# TTL.net
KiCad netlist of a schematic drawn in Altium Designer
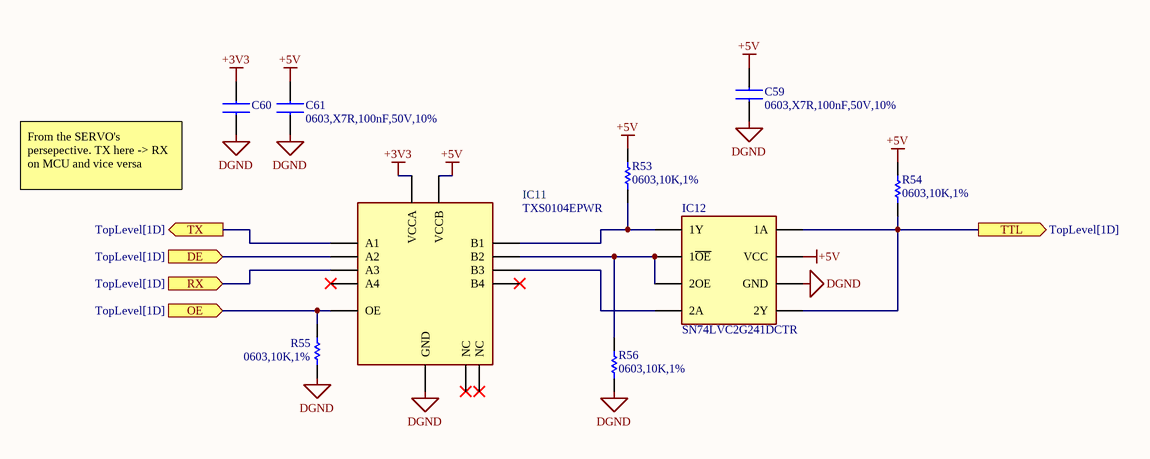
[diagram p0: TTL.SchDoc]

(export (version "E")
  (design (tool "Eeschema 10.0.6"))
  (components
    (comp (ref "C59")
      (value "0603,X7R,100nF,50V,10%")
      (footprint "CAPC1608X90N")
      (description "50V 100nF X7R ±10% 0603 Multilayer Ceramic Capacitors MLCC - SMD/SMT ROHS")
      (fields (field (name "LCSC PART #") "C14663") (field (name "MANU PART #") "CC0603KRX7R9BB104"))
      (libsource (lib "flight-controller") (part "CC0603KRX7R9BB104"))
    )
    (comp (ref "C60")
      (value "0603,X7R,100nF,50V,10%")
      (footprint "CAPC1608X90N")
      (description "50V 100nF X7R ±10% 0603 Multilayer Ceramic Capacitors MLCC - SMD/SMT ROHS")
      (fields (field (name "LCSC PART #") "C14663") (field (name "MANU PART #") "CC0603KRX7R9BB104"))
      (libsource (lib "flight-controller") (part "CC0603KRX7R9BB104"))
    )
    (comp (ref "C61")
      (value "0603,X7R,100nF,50V,10%")
      (footprint "CAPC1608X90N")
      (description "50V 100nF X7R ±10% 0603 Multilayer Ceramic Capacitors MLCC - SMD/SMT ROHS")
      (fields (field (name "LCSC PART #") "C14663") (field (name "MANU PART #") "CC0603KRX7R9BB104"))
      (libsource (lib "flight-controller") (part "CC0603KRX7R9BB104"))
    )
    (comp (ref "IC11")
      (value "TXS0104EPWR")
      (footprint "TXB0104PWR")
      (description "4-Bit Bidirectional Voltage-Level Translator For Open-Drain and Push-Pull Applications")
      (fields (field (name "LCSC PART #") "C44955"))
      (libsource (lib "flight-controller") (part "TXS0104EPWR"))
    )
    (comp (ref "IC12")
      (value "SN74LVC2G241DCTR")
      (footprint "SOP65P400X130-8N")
      (description "SN74LVC2G241 Dual Buffer and Driver with Three-State Outputs")
      (fields (field (name "LCSC PART #") "C2676069"))
      (libsource (lib "flight-controller") (part "SN74LVC2G241DCTR"))
    )
    (comp (ref "R53")
      (value "0603,10K,1%")
      (footprint "RESC1608X90N")
      (description "100mW Thick Film Resistor 75V ±100ppm/℃ ±1% 10kΩ 0603 Chip Resistor - Surface Mount ROHS")
      (fields (field (name "LCSC PART #") "C25804") (field (name "MANU PART #") "0603WAF1002T5E"))
      (libsource (lib "flight-controller") (part "0603WAF1002T5E"))
    )
    (comp (ref "R54")
      (value "0603,10K,1%")
      (footprint "RESC1608X90N")
      (description "100mW Thick Film Resistor 75V ±100ppm/℃ ±1% 10kΩ 0603 Chip Resistor - Surface Mount ROHS")
      (fields (field (name "LCSC PART #") "C25804") (field (name "MANU PART #") "0603WAF1002T5E"))
      (libsource (lib "flight-controller") (part "0603WAF1002T5E"))
    )
    (comp (ref "R55")
      (value "0603,10K,1%")
      (footprint "RESC1608X90N")
      (description "100mW Thick Film Resistor 75V ±100ppm/℃ ±1% 10kΩ 0603 Chip Resistor - Surface Mount ROHS")
      (fields (field (name "LCSC PART #") "C25804") (field (name "MANU PART #") "0603WAF1002T5E"))
      (libsource (lib "flight-controller") (part "0603WAF1002T5E"))
    )
    (comp (ref "R56")
      (value "0603,10K,1%")
      (footprint "RESC1608X90N")
      (description "100mW Thick Film Resistor 75V ±100ppm/℃ ±1% 10kΩ 0603 Chip Resistor - Surface Mount ROHS")
      (fields (field (name "LCSC PART #") "C25804") (field (name "MANU PART #") "0603WAF1002T5E"))
      (libsource (lib "flight-controller") (part "0603WAF1002T5E"))
    )
  )
  (nets
    (net (code "1") (name "+3V3") (class "Default")
      (node (ref "C60") (pin "2") (pinfunction "2_2") (pintype "passive"))
      (node (ref "IC11") (pin "1") (pinfunction "VCCA_1") (pintype "passive"))
    )
    (net (code "2") (name "+5V") (class "Default")
      (node (ref "C59") (pin "2") (pinfunction "2_2") (pintype "passive"))
      (node (ref "C61") (pin "2") (pinfunction "2_2") (pintype "passive"))
      (node (ref "IC11") (pin "14") (pinfunction "VCCB_14") (pintype "passive"))
      (node (ref "IC12") (pin "8") (pinfunction "VCC_8") (pintype "passive"))
      (node (ref "R53") (pin "2") (pinfunction "2_2") (pintype "passive"))
      (node (ref "R54") (pin "2") (pinfunction "2_2") (pintype "passive"))
    )
    (net (code "3") (name "/DE") (class "Default")
      (node (ref "IC11") (pin "3") (pinfunction "A2_3") (pintype "passive"))
    )
    (net (code "4") (name "/OE") (class "Default")
      (node (ref "IC11") (pin "8") (pinfunction "OE_8") (pintype "passive"))
      (node (ref "R55") (pin "2") (pinfunction "2_2") (pintype "passive"))
    )
    (net (code "5") (name "/RX") (class "Default")
      (node (ref "IC11") (pin "4") (pinfunction "A3_4") (pintype "passive"))
    )
    (net (code "6") (name "/TTL") (class "Default")
      (node (ref "IC12") (pin "2") (pinfunction "1A_2") (pintype "passive"))
      (node (ref "IC12") (pin "3") (pinfunction "2Y_3") (pintype "passive"))
      (node (ref "R54") (pin "1") (pinfunction "1_1") (pintype "passive"))
    )
    (net (code "7") (name "/TX") (class "Default")
      (node (ref "IC11") (pin "2") (pinfunction "A1_2") (pintype "passive"))
    )
    (net (code "8") (name "DGND") (class "Default")
      (node (ref "C59") (pin "1") (pinfunction "1_1") (pintype "passive"))
      (node (ref "C60") (pin "1") (pinfunction "1_1") (pintype "passive"))
      (node (ref "C61") (pin "1") (pinfunction "1_1") (pintype "passive"))
      (node (ref "IC11") (pin "7") (pinfunction "GND_7") (pintype "passive"))
      (node (ref "IC12") (pin "4") (pinfunction "GND_4") (pintype "passive"))
      (node (ref "R55") (pin "1") (pinfunction "1_1") (pintype "passive"))
      (node (ref "R56") (pin "1") (pinfunction "1_1") (pintype "passive"))
    )
    (net (code "9") (name "Net-(IC11-B1)") (class "Default")
      (node (ref "IC11") (pin "13") (pinfunction "B1_13") (pintype "passive"))
      (node (ref "IC12") (pin "6") (pinfunction "1Y_6") (pintype "passive"))
      (node (ref "R53") (pin "1") (pinfunction "1_1") (pintype "passive"))
    )
    (net (code "10") (name "Net-(IC11-B2)") (class "Default")
      (node (ref "IC11") (pin "12") (pinfunction "B2_12") (pintype "passive"))
      (node (ref "IC12") (pin "1") (pinfunction "1~{OE}_1") (pintype "passive"))
      (node (ref "IC12") (pin "7") (pinfunction "2OE_7") (pintype "passive"))
      (node (ref "R56") (pin "2") (pinfunction "2_2") (pintype "passive"))
    )
    (net (code "11") (name "Net-(IC11-B3)") (class "Default")
      (node (ref "IC11") (pin "11") (pinfunction "B3_11") (pintype "passive"))
      (node (ref "IC12") (pin "5") (pinfunction "2A_5") (pintype "passive"))
    )
    (net (code "12") (name "unconnected-(IC11-A4-Pad5)") (class "Default")
      (node (ref "IC11") (pin "5") (pinfunction "A4_5") (pintype "passive+no_connect"))
    )
    (net (code "13") (name "unconnected-(IC11-B4-Pad10)") (class "Default")
      (node (ref "IC11") (pin "10") (pinfunction "B4_10") (pintype "passive+no_connect"))
    )
    (net (code "14") (name "unconnected-(IC11-NC-Pad6)") (class "Default")
      (node (ref "IC11") (pin "6") (pinfunction "NC_6") (pintype "passive+no_connect"))
    )
    (net (code "15") (name "unconnected-(IC11-NC-Pad9)") (class "Default")
      (node (ref "IC11") (pin "9") (pinfunction "NC_9") (pintype "passive+no_connect"))
    )
  )
)
